# EEPROM_Programmer.net
KiCad netlist of a schematic drawn in EAGLE
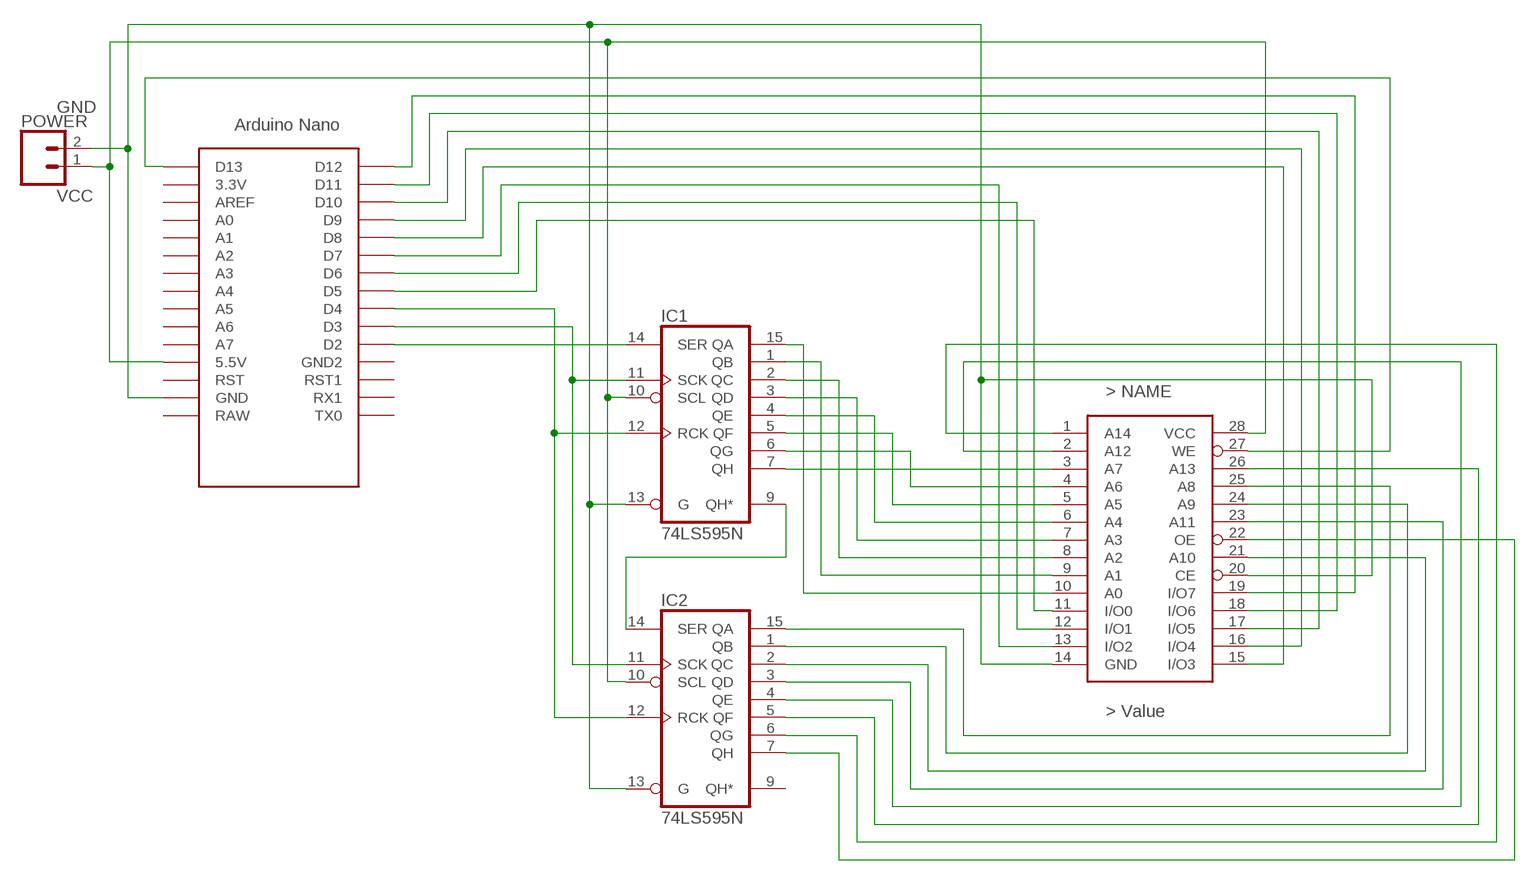
[diagram p0: schematic, sheet 1]

(export (version "E")
  (design (tool "Eeschema 10.0.6"))
  (components
    (comp (ref "EEPROM")
      (value "28C256")
      (footprint "eagle-import:DIP1722W26P254L3450H508Q28B")
      (libsource (lib "eagle-import") (part "28C256"))
    )
    (comp (ref "IC1")
      (value "74LS595N")
      (footprint "eagle-import:DIL16")
      (libsource (lib "eagle-import") (part "74595NLS"))
    )
    (comp (ref "IC2")
      (value "74LS595N")
      (footprint "eagle-import:DIL16")
      (libsource (lib "eagle-import") (part "74595NLS"))
    )
    (comp (ref "POWER")
      (value "CONN_02POGO_PIN_HOLES_ONLY")
      (footprint "eagle-import:1X02_PP_HOLES_ONLY")
      (libsource (lib "eagle-import") (part "CONN_02POGO_PIN_HOLES_ONLY"))
    )
    (comp (ref "U$1")
      (value "NANO")
      (footprint "eagle-import:NANO")
      (libsource (lib "eagle-import") (part "NANO"))
    )
  )
  (nets
    (net (code "1") (name "/GND") (class "Default")
      (node (ref "EEPROM") (pin "14") (pinfunction "GND_14") (pintype "bidirectional"))
      (node (ref "EEPROM") (pin "20") (pinfunction "CE_20") (pintype "bidirectional"))
      (node (ref "IC1") (pin "13") (pinfunction "G_13") (pintype "input"))
      (node (ref "IC2") (pin "13") (pinfunction "G_13") (pintype "input"))
      (node (ref "POWER") (pin "2") (pinfunction "2_2") (pintype "passive"))
      (node (ref "U$1") (pin "GND") (pinfunction "GND_GND") (pintype "bidirectional"))
    )
    (net (code "2") (name "/VCC") (class "Default")
      (node (ref "EEPROM") (pin "28") (pinfunction "VCC_28") (pintype "bidirectional"))
      (node (ref "IC1") (pin "10") (pinfunction "SCL_10") (pintype "input"))
      (node (ref "IC2") (pin "10") (pinfunction "SCL_10") (pintype "input"))
      (node (ref "POWER") (pin "1") (pinfunction "1_1") (pintype "passive"))
      (node (ref "U$1") (pin "5V") (pinfunction "5.5V_5V") (pintype "bidirectional"))
    )
    (net (code "3") (name "Net-(EEPROM-A0)") (class "Default")
      (node (ref "EEPROM") (pin "10") (pinfunction "A0_10") (pintype "bidirectional"))
      (node (ref "IC1") (pin "15") (pinfunction "QA_15") (pintype "tri_state"))
    )
    (net (code "4") (name "Net-(EEPROM-A1)") (class "Default")
      (node (ref "EEPROM") (pin "9") (pinfunction "A1_9") (pintype "bidirectional"))
      (node (ref "IC1") (pin "1") (pinfunction "QB_1") (pintype "tri_state"))
    )
    (net (code "5") (name "Net-(EEPROM-A2)") (class "Default")
      (node (ref "EEPROM") (pin "8") (pinfunction "A2_8") (pintype "bidirectional"))
      (node (ref "IC1") (pin "2") (pinfunction "QC_2") (pintype "tri_state"))
    )
    (net (code "6") (name "Net-(EEPROM-A3)") (class "Default")
      (node (ref "EEPROM") (pin "7") (pinfunction "A3_7") (pintype "bidirectional"))
      (node (ref "IC1") (pin "3") (pinfunction "QD_3") (pintype "tri_state"))
    )
    (net (code "7") (name "Net-(EEPROM-A4)") (class "Default")
      (node (ref "EEPROM") (pin "6") (pinfunction "A4_6") (pintype "bidirectional"))
      (node (ref "IC1") (pin "4") (pinfunction "QE_4") (pintype "tri_state"))
    )
    (net (code "8") (name "Net-(EEPROM-A5)") (class "Default")
      (node (ref "EEPROM") (pin "5") (pinfunction "A5_5") (pintype "bidirectional"))
      (node (ref "IC1") (pin "5") (pinfunction "QF_5") (pintype "tri_state"))
    )
    (net (code "9") (name "Net-(EEPROM-A6)") (class "Default")
      (node (ref "EEPROM") (pin "4") (pinfunction "A6_4") (pintype "bidirectional"))
      (node (ref "IC1") (pin "6") (pinfunction "QG_6") (pintype "tri_state"))
    )
    (net (code "10") (name "Net-(EEPROM-A7)") (class "Default")
      (node (ref "EEPROM") (pin "3") (pinfunction "A7_3") (pintype "bidirectional"))
      (node (ref "IC1") (pin "7") (pinfunction "QH_7") (pintype "tri_state"))
    )
    (net (code "11") (name "Net-(EEPROM-A8)") (class "Default")
      (node (ref "EEPROM") (pin "25") (pinfunction "A8_25") (pintype "bidirectional"))
      (node (ref "IC2") (pin "15") (pinfunction "QA_15") (pintype "tri_state"))
    )
    (net (code "12") (name "Net-(EEPROM-A9)") (class "Default")
      (node (ref "EEPROM") (pin "24") (pinfunction "A9_24") (pintype "bidirectional"))
      (node (ref "IC2") (pin "1") (pinfunction "QB_1") (pintype "tri_state"))
    )
    (net (code "13") (name "Net-(EEPROM-A10)") (class "Default")
      (node (ref "EEPROM") (pin "21") (pinfunction "A10_21") (pintype "bidirectional"))
      (node (ref "IC2") (pin "2") (pinfunction "QC_2") (pintype "tri_state"))
    )
    (net (code "14") (name "Net-(EEPROM-A11)") (class "Default")
      (node (ref "EEPROM") (pin "23") (pinfunction "A11_23") (pintype "bidirectional"))
      (node (ref "IC2") (pin "3") (pinfunction "QD_3") (pintype "tri_state"))
    )
    (net (code "15") (name "Net-(EEPROM-A12)") (class "Default")
      (node (ref "EEPROM") (pin "2") (pinfunction "A12_2") (pintype "bidirectional"))
      (node (ref "IC2") (pin "4") (pinfunction "QE_4") (pintype "tri_state"))
    )
    (net (code "16") (name "Net-(EEPROM-A13)") (class "Default")
      (node (ref "EEPROM") (pin "26") (pinfunction "A13_26") (pintype "bidirectional"))
      (node (ref "IC2") (pin "5") (pinfunction "QF_5") (pintype "tri_state"))
    )
    (net (code "17") (name "Net-(EEPROM-A14)") (class "Default")
      (node (ref "EEPROM") (pin "1") (pinfunction "A14_1") (pintype "bidirectional"))
      (node (ref "IC2") (pin "6") (pinfunction "QG_6") (pintype "tri_state"))
    )
    (net (code "18") (name "Net-(EEPROM-I{slash}O0)") (class "Default")
      (node (ref "EEPROM") (pin "11") (pinfunction "I/O0_11") (pintype "bidirectional"))
      (node (ref "U$1") (pin "D5") (pinfunction "D5_D5") (pintype "bidirectional"))
    )
    (net (code "19") (name "Net-(EEPROM-I{slash}O1)") (class "Default")
      (node (ref "EEPROM") (pin "12") (pinfunction "I/O1_12") (pintype "bidirectional"))
      (node (ref "U$1") (pin "D6") (pinfunction "D6_D6") (pintype "bidirectional"))
    )
    (net (code "20") (name "Net-(EEPROM-I{slash}O2)") (class "Default")
      (node (ref "EEPROM") (pin "13") (pinfunction "I/O2_13") (pintype "bidirectional"))
      (node (ref "U$1") (pin "D7") (pinfunction "D7_D7") (pintype "bidirectional"))
    )
    (net (code "21") (name "Net-(EEPROM-I{slash}O3)") (class "Default")
      (node (ref "EEPROM") (pin "15") (pinfunction "I/O3_15") (pintype "bidirectional"))
      (node (ref "U$1") (pin "D8") (pinfunction "D8_D8") (pintype "bidirectional"))
    )
    (net (code "22") (name "Net-(EEPROM-I{slash}O4)") (class "Default")
      (node (ref "EEPROM") (pin "16") (pinfunction "I/O4_16") (pintype "bidirectional"))
      (node (ref "U$1") (pin "D9") (pinfunction "D9_D9") (pintype "bidirectional"))
    )
    (net (code "23") (name "Net-(EEPROM-I{slash}O5)") (class "Default")
      (node (ref "EEPROM") (pin "17") (pinfunction "I/O5_17") (pintype "bidirectional"))
      (node (ref "U$1") (pin "D10") (pinfunction "D10_D10") (pintype "bidirectional"))
    )
    (net (code "24") (name "Net-(EEPROM-I{slash}O6)") (class "Default")
      (node (ref "EEPROM") (pin "18") (pinfunction "I/O6_18") (pintype "bidirectional"))
      (node (ref "U$1") (pin "D11") (pinfunction "D11_D11") (pintype "bidirectional"))
    )
    (net (code "25") (name "Net-(EEPROM-I{slash}O7)") (class "Default")
      (node (ref "EEPROM") (pin "19") (pinfunction "I/O7_19") (pintype "bidirectional"))
      (node (ref "U$1") (pin "D12") (pinfunction "D12_D12") (pintype "bidirectional"))
    )
    (net (code "26") (name "Net-(EEPROM-OE)") (class "Default")
      (node (ref "EEPROM") (pin "22") (pinfunction "OE_22") (pintype "bidirectional"))
      (node (ref "IC2") (pin "7") (pinfunction "QH_7") (pintype "tri_state"))
    )
    (net (code "27") (name "Net-(EEPROM-WE)") (class "Default")
      (node (ref "EEPROM") (pin "27") (pinfunction "WE_27") (pintype "bidirectional"))
      (node (ref "U$1") (pin "D13") (pinfunction "D13_D13") (pintype "bidirectional"))
    )
    (net (code "28") (name "Net-(IC1A-QH*)") (class "Default")
      (node (ref "IC1") (pin "9") (pinfunction "QH*_9") (pintype "tri_state"))
      (node (ref "IC2") (pin "14") (pinfunction "SER_14") (pintype "input"))
    )
    (net (code "29") (name "Net-(IC1A-RCK)") (class "Default")
      (node (ref "IC1") (pin "12") (pinfunction "RCK_12") (pintype "input"))
      (node (ref "IC2") (pin "12") (pinfunction "RCK_12") (pintype "input"))
      (node (ref "U$1") (pin "D4") (pinfunction "D4_D4") (pintype "bidirectional"))
    )
    (net (code "30") (name "Net-(IC1A-SCK)") (class "Default")
      (node (ref "IC1") (pin "11") (pinfunction "SCK_11") (pintype "input"))
      (node (ref "IC2") (pin "11") (pinfunction "SCK_11") (pintype "input"))
      (node (ref "U$1") (pin "D3") (pinfunction "D3_D3") (pintype "bidirectional"))
    )
    (net (code "31") (name "Net-(IC1A-SER)") (class "Default")
      (node (ref "IC1") (pin "14") (pinfunction "SER_14") (pintype "input"))
      (node (ref "U$1") (pin "D2") (pinfunction "D2_D2") (pintype "bidirectional"))
    )
    (net (code "32") (name "unconnected-(IC2A-QH*-Pad9)") (class "Default")
      (node (ref "IC2") (pin "9") (pinfunction "QH*_9") (pintype "tri_state"))
    )
    (net (code "33") (name "unconnected-(U$1-GND2-PadGND1)") (class "Default")
      (node (ref "U$1") (pin "GND1") (pinfunction "GND2_GND1") (pintype "bidirectional"))
    )
    (net (code "34") (name "unconnected-(U$1-Pad3.3V)") (class "Default")
      (node (ref "U$1") (pin "3.3V") (pinfunction "3.3V_3.3V") (pintype "bidirectional"))
    )
    (net (code "35") (name "unconnected-(U$1-PadA0)") (class "Default")
      (node (ref "U$1") (pin "A0") (pinfunction "A0_A0") (pintype "bidirectional"))
    )
    (net (code "36") (name "unconnected-(U$1-PadA1)") (class "Default")
      (node (ref "U$1") (pin "A1") (pinfunction "A1_A1") (pintype "bidirectional"))
    )
    (net (code "37") (name "unconnected-(U$1-PadA2)") (class "Default")
      (node (ref "U$1") (pin "A2") (pinfunction "A2_A2") (pintype "bidirectional"))
    )
    (net (code "38") (name "unconnected-(U$1-PadA3)") (class "Default")
      (node (ref "U$1") (pin "A3") (pinfunction "A3_A3") (pintype "bidirectional"))
    )
    (net (code "39") (name "unconnected-(U$1-PadA4)") (class "Default")
      (node (ref "U$1") (pin "A4") (pinfunction "A4_A4") (pintype "bidirectional"))
    )
    (net (code "40") (name "unconnected-(U$1-PadA5)") (class "Default")
      (node (ref "U$1") (pin "A5") (pinfunction "A5_A5") (pintype "bidirectional"))
    )
    (net (code "41") (name "unconnected-(U$1-PadA6)") (class "Default")
      (node (ref "U$1") (pin "A6") (pinfunction "A6_A6") (pintype "bidirectional"))
    )
    (net (code "42") (name "unconnected-(U$1-PadA7)") (class "Default")
      (node (ref "U$1") (pin "A7") (pinfunction "A7_A7") (pintype "bidirectional"))
    )
    (net (code "43") (name "unconnected-(U$1-PadAREF)") (class "Default")
      (node (ref "U$1") (pin "AREF") (pinfunction "AREF_AREF") (pintype "bidirectional"))
    )
    (net (code "44") (name "unconnected-(U$1-PadICSP1)") (class "Default")
      (node (ref "U$1") (pin "ICSP1") (pinfunction "ICSP1_ICSP1") (pintype "bidirectional"))
    )
    (net (code "45") (name "unconnected-(U$1-PadICSP2)") (class "Default")
      (node (ref "U$1") (pin "ICSP2") (pinfunction "ICSP2_ICSP2") (pintype "bidirectional"))
    )
    (net (code "46") (name "unconnected-(U$1-PadICSP3)") (class "Default")
      (node (ref "U$1") (pin "ICSP3") (pinfunction "ICSP3_ICSP3") (pintype "bidirectional"))
    )
    (net (code "47") (name "unconnected-(U$1-PadICSP4)") (class "Default")
      (node (ref "U$1") (pin "ICSP4") (pinfunction "ICSP4_ICSP4") (pintype "bidirectional"))
    )
    (net (code "48") (name "unconnected-(U$1-PadICSP5)") (class "Default")
      (node (ref "U$1") (pin "ICSP5") (pinfunction "ICSP5_ICSP5") (pintype "bidirectional"))
    )
    (net (code "49") (name "unconnected-(U$1-PadICSP6)") (class "Default")
      (node (ref "U$1") (pin "ICSP6") (pinfunction "ICSP6_ICSP6") (pintype "bidirectional"))
    )
    (net (code "50") (name "unconnected-(U$1-PadRAW)") (class "Default")
      (node (ref "U$1") (pin "RAW") (pinfunction "RAW_RAW") (pintype "bidirectional"))
    )
    (net (code "51") (name "unconnected-(U$1-PadRST)") (class "Default")
      (node (ref "U$1") (pin "RST") (pinfunction "RST_RST") (pintype "bidirectional"))
    )
    (net (code "52") (name "unconnected-(U$1-PadRST1)") (class "Default")
      (node (ref "U$1") (pin "RST1") (pinfunction "RST1_RST1") (pintype "bidirectional"))
    )
    (net (code "53") (name "unconnected-(U$1-PadRX1)") (class "Default")
      (node (ref "U$1") (pin "RX1") (pinfunction "RX1_RX1") (pintype "bidirectional"))
    )
    (net (code "54") (name "unconnected-(U$1-PadTX0)") (class "Default")
      (node (ref "U$1") (pin "TX0") (pinfunction "TX0_TX0") (pintype "bidirectional"))
    )
  )
)
